# ESP-12F_Programming_Board-2.net
KiCad netlist of a schematic drawn in EAGLE
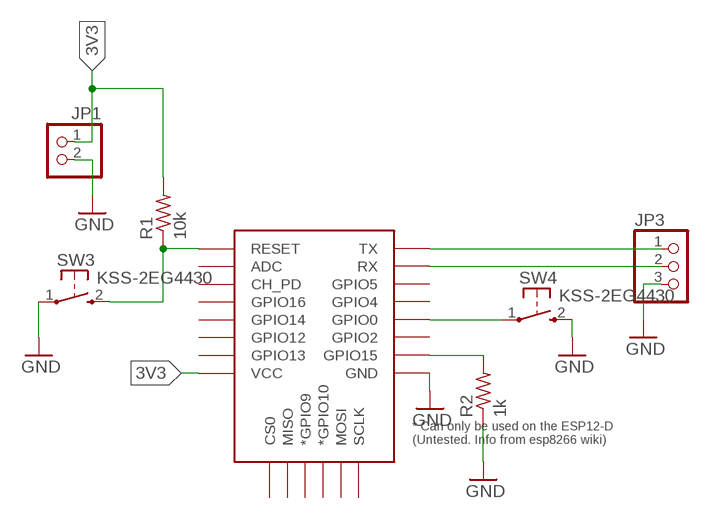
[diagram p0: schematic, sheet 1]

(export (version "E")
  (design (tool "Eeschema 10.0.6"))
  (components
    (comp (ref "JP1")
      (value "PINHD-1X2")
      (footprint "eagle-import:1X02")
      (libsource (lib "eagle-import") (part "PINHD-1X2"))
    )
    (comp (ref "JP3")
      (value "PINHD-1X3")
      (footprint "eagle-import:1X03")
      (libsource (lib "eagle-import") (part "PINHD-1X3"))
    )
    (comp (ref "R1")
      (value "10k")
      (footprint "eagle-import:R0805")
      (libsource (lib "eagle-import") (part "R-US_R0805"))
    )
    (comp (ref "R2")
      (value "1k")
      (footprint "eagle-import:R0805")
      (libsource (lib "eagle-import") (part "R-US_R0805"))
    )
    (comp (ref "SW3")
      (value "KSS-2EG4430")
      (footprint "eagle-import:KSS-2EG4430")
      (libsource (lib "eagle-import") (part "KSS-2EG4430"))
    )
    (comp (ref "SW4")
      (value "KSS-2EG4430")
      (footprint "eagle-import:KSS-2EG4430")
      (libsource (lib "eagle-import") (part "KSS-2EG4430"))
    )
    (comp (ref "U1")
      (value "ESP12ESMD")
      (footprint "eagle-import:ESP12E-SMD")
      (libsource (lib "eagle-import") (part "ESP12ESMD"))
    )
  )
  (nets
    (net (code "1") (name "3V3") (class "Default")
      (node (ref "JP1") (pin "1") (pinfunction "1_1") (pintype "passive"))
      (node (ref "R1") (pin "2") (pinfunction "2_2") (pintype "passive"))
      (node (ref "U1") (pin "VCC") (pinfunction "VCC_VCC") (pintype "bidirectional"))
    )
    (net (code "2") (name "GND") (class "Default")
      (node (ref "JP1") (pin "2") (pinfunction "2_2") (pintype "passive"))
      (node (ref "JP3") (pin "3") (pinfunction "3_3") (pintype "passive"))
      (node (ref "R2") (pin "1") (pinfunction "1_1") (pintype "passive"))
      (node (ref "SW3") (pin "1") (pinfunction "P_1") (pintype "passive"))
      (node (ref "SW4") (pin "2") (pinfunction "S_2") (pintype "passive"))
      (node (ref "U1") (pin "GND") (pinfunction "GND_GND") (pintype "bidirectional"))
    )
    (net (code "3") (name "Net-(R2-Pad2)") (class "Default")
      (node (ref "R2") (pin "2") (pinfunction "2_2") (pintype "passive"))
      (node (ref "U1") (pin "GPIO15") (pinfunction "GPIO15_GPIO15") (pintype "bidirectional"))
    )
    (net (code "4") (name "Net-(SW3-S)") (class "Default")
      (node (ref "R1") (pin "1") (pinfunction "1_1") (pintype "passive"))
      (node (ref "SW3") (pin "2") (pinfunction "S_2") (pintype "passive"))
      (node (ref "U1") (pin "RESET") (pinfunction "RESET_RESET") (pintype "bidirectional"))
    )
    (net (code "5") (name "Net-(SW4-P)") (class "Default")
      (node (ref "SW4") (pin "1") (pinfunction "P_1") (pintype "passive"))
      (node (ref "U1") (pin "GPIO0") (pinfunction "GPIO0_GPIO0") (pintype "bidirectional"))
    )
    (net (code "6") (name "Net-(U1-RX)") (class "Default")
      (node (ref "JP3") (pin "2") (pinfunction "2_2") (pintype "passive"))
      (node (ref "U1") (pin "RXD0") (pinfunction "RX_RXD0") (pintype "bidirectional"))
    )
    (net (code "7") (name "Net-(U1-TX)") (class "Default")
      (node (ref "JP3") (pin "1") (pinfunction "1_1") (pintype "passive"))
      (node (ref "U1") (pin "TXD0") (pinfunction "TX_TXD0") (pintype "bidirectional"))
    )
    (net (code "8") (name "unconnected-(U1-*GPIO9-PadGPIO9)") (class "Default")
      (node (ref "U1") (pin "GPIO9") (pinfunction "*GPIO9_GPIO9") (pintype "bidirectional"))
    )
    (net (code "9") (name "unconnected-(U1-*GPIO10-PadGPIO10)") (class "Default")
      (node (ref "U1") (pin "GPIO10") (pinfunction "*GPIO10_GPIO10") (pintype "bidirectional"))
    )
    (net (code "10") (name "unconnected-(U1-PadADC)") (class "Default")
      (node (ref "U1") (pin "ADC") (pinfunction "ADC_ADC") (pintype "bidirectional"))
    )
    (net (code "11") (name "unconnected-(U1-PadCH_PD)") (class "Default")
      (node (ref "U1") (pin "CH_PD") (pinfunction "CH_PD_CH_PD") (pintype "bidirectional"))
    )
    (net (code "12") (name "unconnected-(U1-PadCS0)") (class "Default")
      (node (ref "U1") (pin "CS0") (pinfunction "CS0_CS0") (pintype "bidirectional"))
    )
    (net (code "13") (name "unconnected-(U1-PadGPIO2)") (class "Default")
      (node (ref "U1") (pin "GPIO2") (pinfunction "GPIO2_GPIO2") (pintype "bidirectional"))
    )
    (net (code "14") (name "unconnected-(U1-PadGPIO4)") (class "Default")
      (node (ref "U1") (pin "GPIO4") (pinfunction "GPIO4_GPIO4") (pintype "bidirectional"))
    )
    (net (code "15") (name "unconnected-(U1-PadGPIO5)") (class "Default")
      (node (ref "U1") (pin "GPIO5") (pinfunction "GPIO5_GPIO5") (pintype "bidirectional"))
    )
    (net (code "16") (name "unconnected-(U1-PadGPIO12)") (class "Default")
      (node (ref "U1") (pin "GPIO12") (pinfunction "GPIO12_GPIO12") (pintype "bidirectional"))
    )
    (net (code "17") (name "unconnected-(U1-PadGPIO13)") (class "Default")
      (node (ref "U1") (pin "GPIO13") (pinfunction "GPIO13_GPIO13") (pintype "bidirectional"))
    )
    (net (code "18") (name "unconnected-(U1-PadGPIO14)") (class "Default")
      (node (ref "U1") (pin "GPIO14") (pinfunction "GPIO14_GPIO14") (pintype "bidirectional"))
    )
    (net (code "19") (name "unconnected-(U1-PadGPIO16)") (class "Default")
      (node (ref "U1") (pin "GPIO16") (pinfunction "GPIO16_GPIO16") (pintype "bidirectional"))
    )
    (net (code "20") (name "unconnected-(U1-PadMISO)") (class "Default")
      (node (ref "U1") (pin "MISO") (pinfunction "MISO_MISO") (pintype "bidirectional"))
    )
    (net (code "21") (name "unconnected-(U1-PadMOSI)") (class "Default")
      (node (ref "U1") (pin "MOSI") (pinfunction "MOSI_MOSI") (pintype "bidirectional"))
    )
    (net (code "22") (name "unconnected-(U1-PadSCLK)") (class "Default")
      (node (ref "U1") (pin "SCLK") (pinfunction "SCLK_SCLK") (pintype "bidirectional"))
    )
  )
)
